# schematic.net
KiCad netlist of a schematic drawn in EAGLE
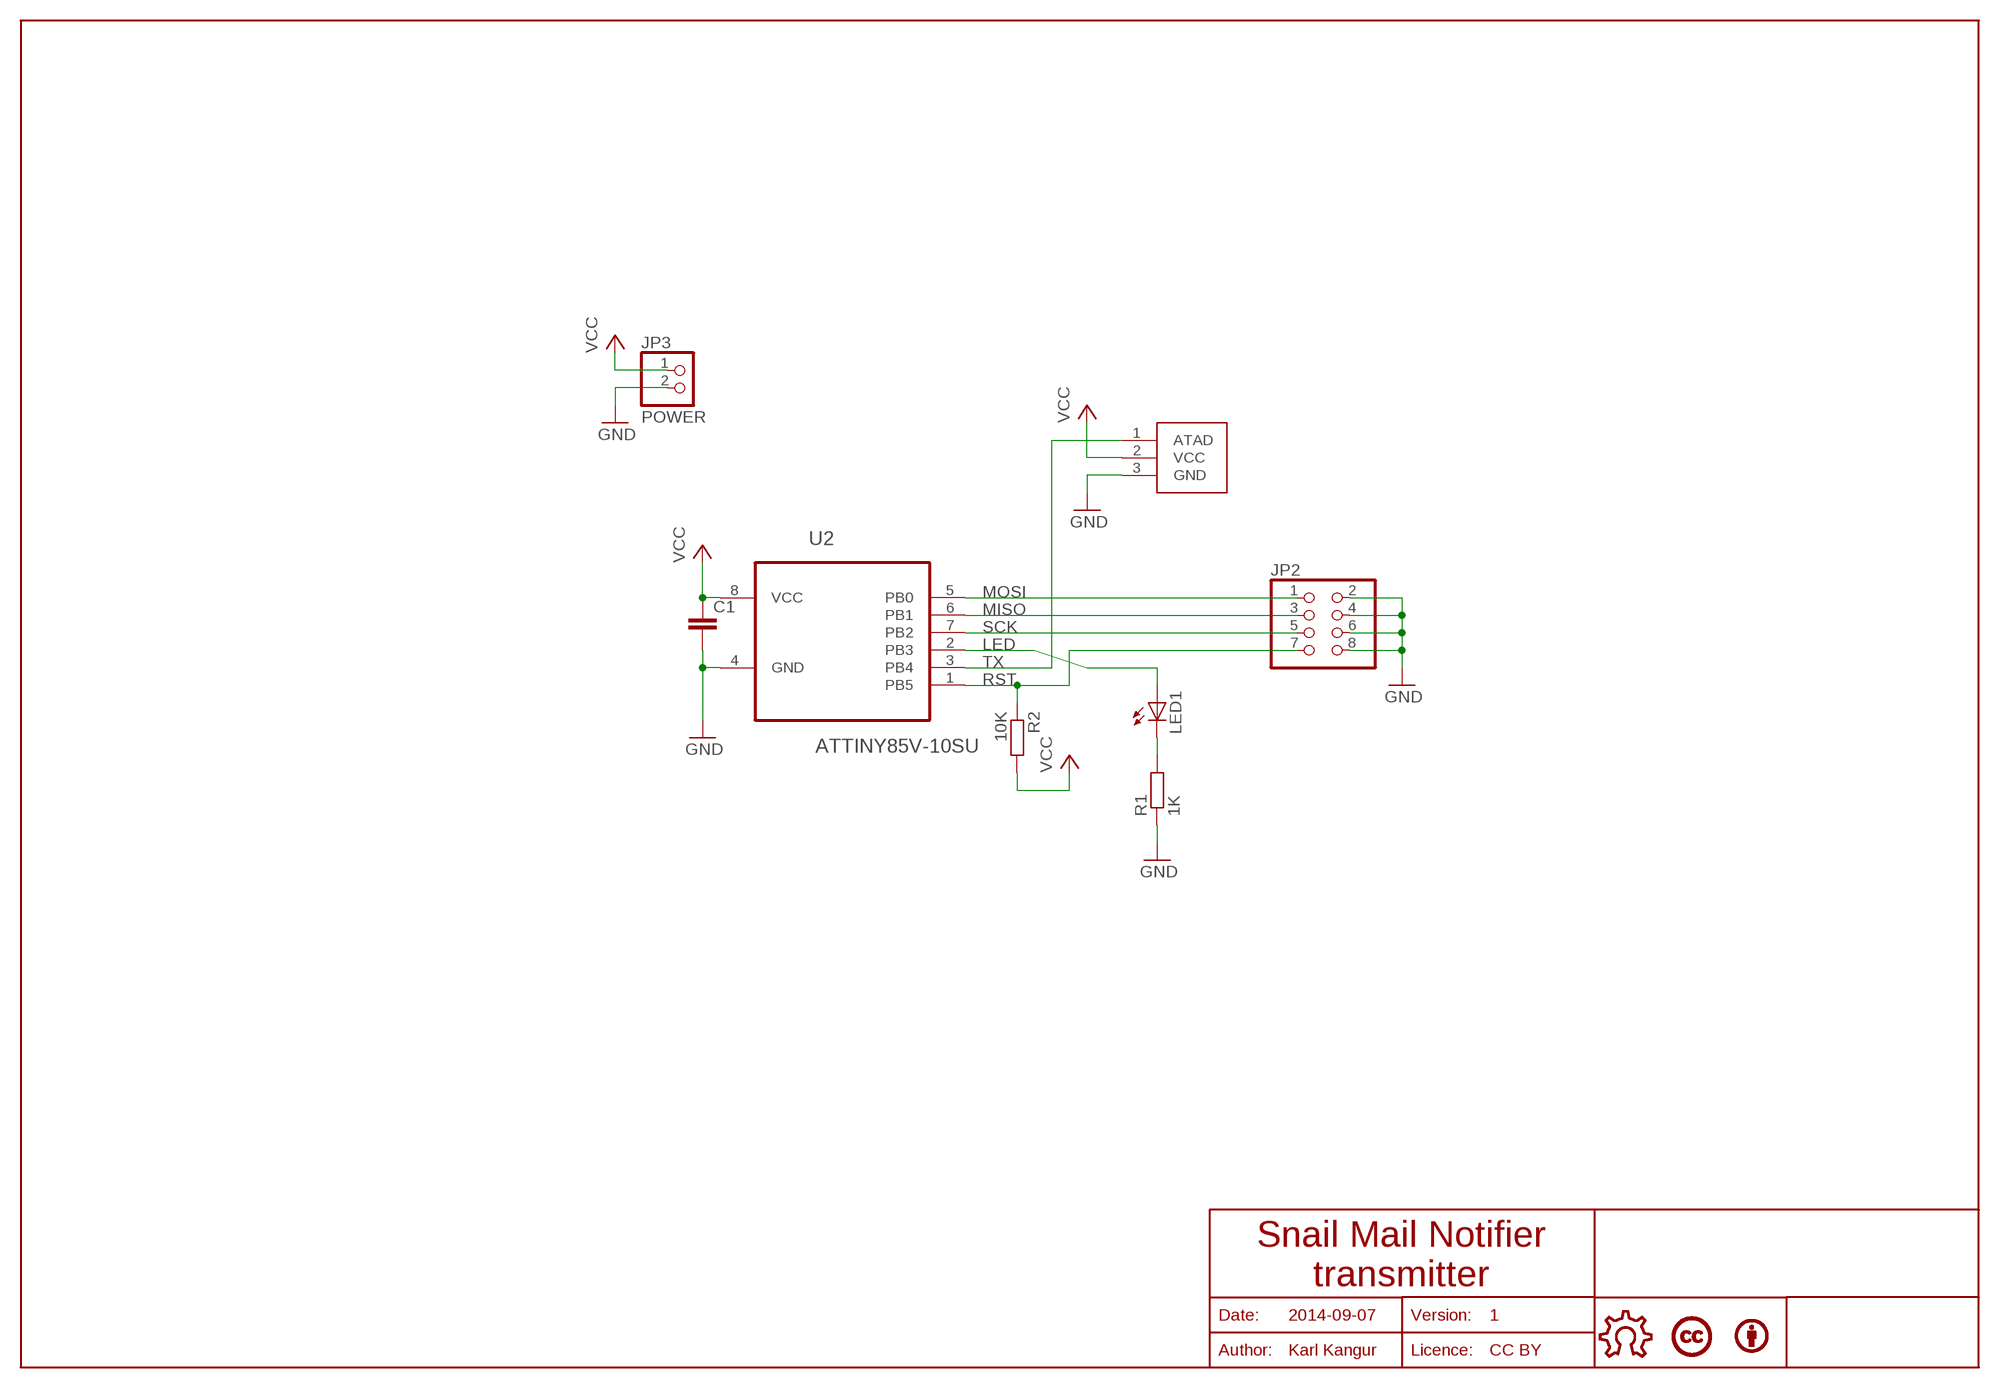
[diagram p0: schematic, sheet 1]

(export (version "E")
  (design (tool "Eeschema 10.0.6"))
  (components
    (comp (ref "BY1")
      (value "BYBOTTOM")
      (footprint "eagle-import:BY")
      (libsource (lib "eagle-import") (part "BYBOTTOM"))
    )
    (comp (ref "C1")
      (value "C-EUC0805")
      (footprint "eagle-import:C0805")
      (libsource (lib "eagle-import") (part "C-EUC0805"))
    )
    (comp (ref "JP2")
      (value "PINHD-2X4")
      (footprint "eagle-import:2X04")
      (libsource (lib "eagle-import") (part "PINHD-2X4"))
    )
    (comp (ref "JP3")
      (value "POWER")
      (footprint "eagle-import:1X02")
      (libsource (lib "eagle-import") (part "PINHD-1X2"))
    )
    (comp (ref "LED1")
      (value "LED3MM")
      (footprint "eagle-import:LED3MM")
      (libsource (lib "eagle-import") (part "LED3MM"))
    )
    (comp (ref "LICENCE1")
      (value "LICENCECC-BOTTOM")
      (footprint "eagle-import:CREATIVE-COMMONS")
      (libsource (lib "eagle-import") (part "LICENCECC-BOTTOM"))
    )
    (comp (ref "R1")
      (value "1K")
      (footprint "eagle-import:R0805")
      (libsource (lib "eagle-import") (part "R-EU_R0805"))
    )
    (comp (ref "R2")
      (value "10K")
      (footprint "eagle-import:R0805")
      (libsource (lib "eagle-import") (part "R-EU_R0805"))
    )
    (comp (ref "U$1")
      (value "RF_LINK_TRANSMITTER")
      (footprint "eagle-import:RF_LINK_TRANSMITTER")
      (libsource (lib "eagle-import") (part "RF_LINK_TRANSMITTER"))
    )
    (comp (ref "U$5")
      (value "OPEN-HARDWARE-LOGOBOTTOM-SMALL")
      (footprint "eagle-import:OPEN-HARDWARE-BOTTOM-SMALL")
      (libsource (lib "eagle-import") (part "OPEN-HARDWARE-LOGOBOTTOM-SMALL"))
    )
    (comp (ref "U2")
      (value "ATTINY85V-10SU")
      (footprint "eagle-import:SOIC127P798X216-8N")
      (libsource (lib "eagle-import") (part "ATTINY85V-10SU"))
    )
  )
  (nets
    (net (code "1") (name "/LED") (class "Default")
      (node (ref "LED1") (pin "A") (pinfunction "A_A") (pintype "passive"))
      (node (ref "U2") (pin "2") (pinfunction "PB3_2") (pintype "bidirectional"))
    )
    (net (code "2") (name "/MISO") (class "Default")
      (node (ref "JP2") (pin "3") (pinfunction "3_3") (pintype "passive"))
      (node (ref "U2") (pin "6") (pinfunction "PB1_6") (pintype "bidirectional"))
    )
    (net (code "3") (name "/MOSI") (class "Default")
      (node (ref "JP2") (pin "1") (pinfunction "1_1") (pintype "passive"))
      (node (ref "U2") (pin "5") (pinfunction "PB0_5") (pintype "bidirectional"))
    )
    (net (code "4") (name "/RST") (class "Default")
      (node (ref "JP2") (pin "7") (pinfunction "7_7") (pintype "passive"))
      (node (ref "R2") (pin "1") (pinfunction "1_1") (pintype "passive"))
      (node (ref "U2") (pin "1") (pinfunction "PB5_1") (pintype "bidirectional"))
    )
    (net (code "5") (name "/SCK") (class "Default")
      (node (ref "JP2") (pin "5") (pinfunction "5_5") (pintype "passive"))
      (node (ref "U2") (pin "7") (pinfunction "PB2_7") (pintype "bidirectional"))
    )
    (net (code "6") (name "/TX") (class "Default")
      (node (ref "U$1") (pin "1") (pinfunction "ATAD_1") (pintype "bidirectional"))
      (node (ref "U2") (pin "3") (pinfunction "PB4_3") (pintype "bidirectional"))
    )
    (net (code "7") (name "GND") (class "Default")
      (node (ref "C1") (pin "2") (pinfunction "2_2") (pintype "passive"))
      (node (ref "JP2") (pin "2") (pinfunction "2_2") (pintype "passive"))
      (node (ref "JP2") (pin "4") (pinfunction "4_4") (pintype "passive"))
      (node (ref "JP2") (pin "6") (pinfunction "6_6") (pintype "passive"))
      (node (ref "JP2") (pin "8") (pinfunction "8_8") (pintype "passive"))
      (node (ref "JP3") (pin "2") (pinfunction "2_2") (pintype "passive"))
      (node (ref "R1") (pin "1") (pinfunction "1_1") (pintype "passive"))
      (node (ref "U$1") (pin "3") (pinfunction "GND_3") (pintype "bidirectional"))
      (node (ref "U2") (pin "4") (pinfunction "GND_4") (pintype "passive"))
    )
    (net (code "8") (name "Net-(LED1-C)") (class "Default")
      (node (ref "LED1") (pin "K") (pinfunction "C_K") (pintype "passive"))
      (node (ref "R1") (pin "2") (pinfunction "2_2") (pintype "passive"))
    )
    (net (code "9") (name "VCC") (class "Default")
      (node (ref "C1") (pin "1") (pinfunction "1_1") (pintype "passive"))
      (node (ref "JP3") (pin "1") (pinfunction "1_1") (pintype "passive"))
      (node (ref "R2") (pin "2") (pinfunction "2_2") (pintype "passive"))
      (node (ref "U$1") (pin "2") (pinfunction "VCC_2") (pintype "bidirectional"))
      (node (ref "U2") (pin "8") (pinfunction "VCC_8") (pintype "power_in"))
    )
  )
)
